# electronic_load_V02_0.net
KiCad netlist of a schematic drawn in EAGLE
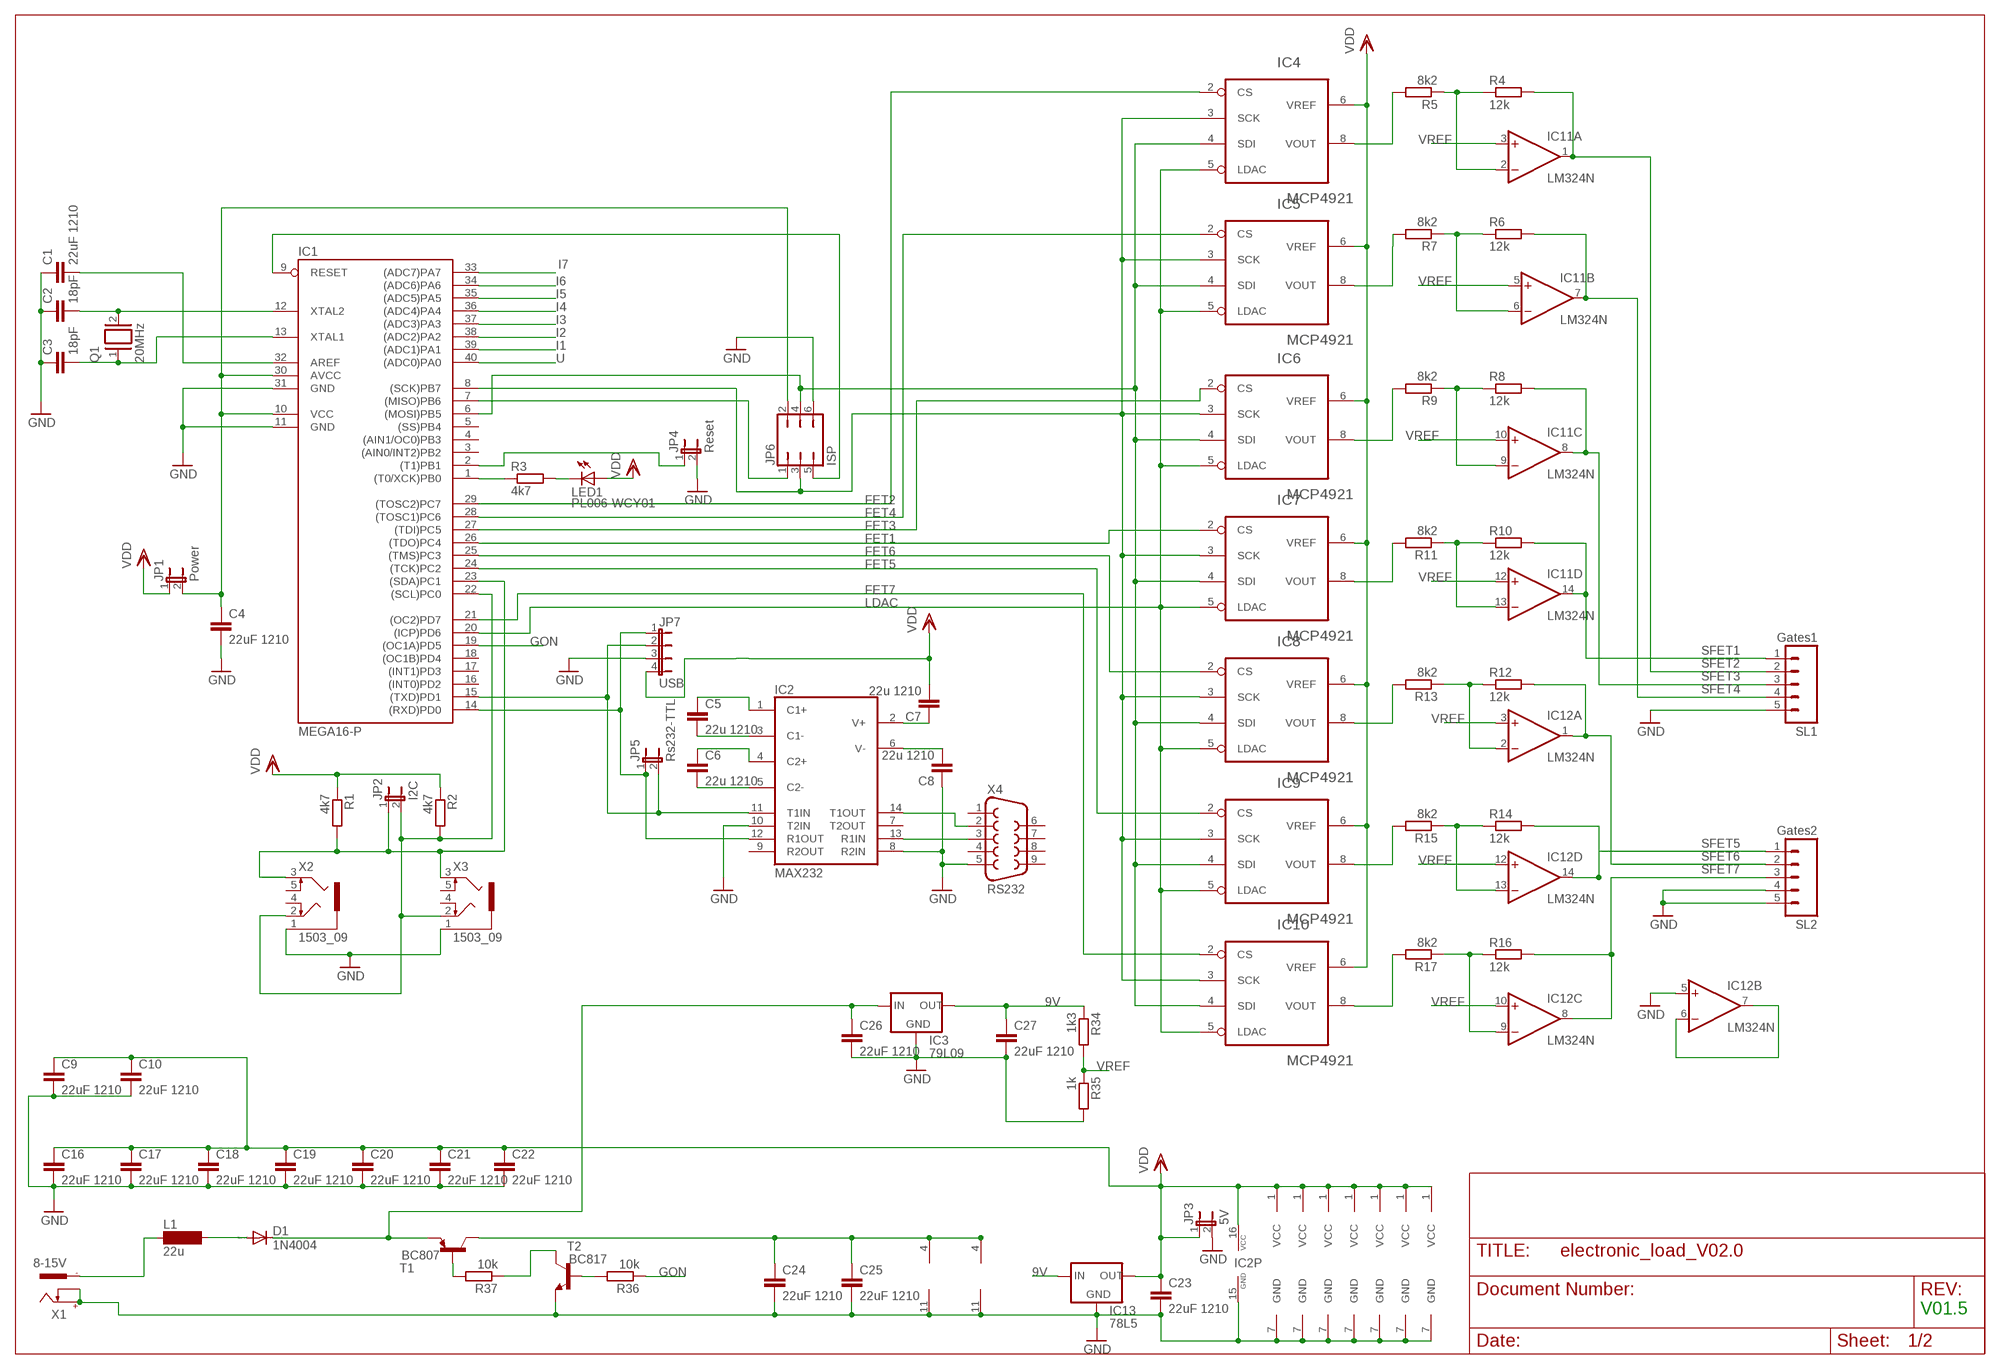
[diagram p0: schematic, sheet 1]
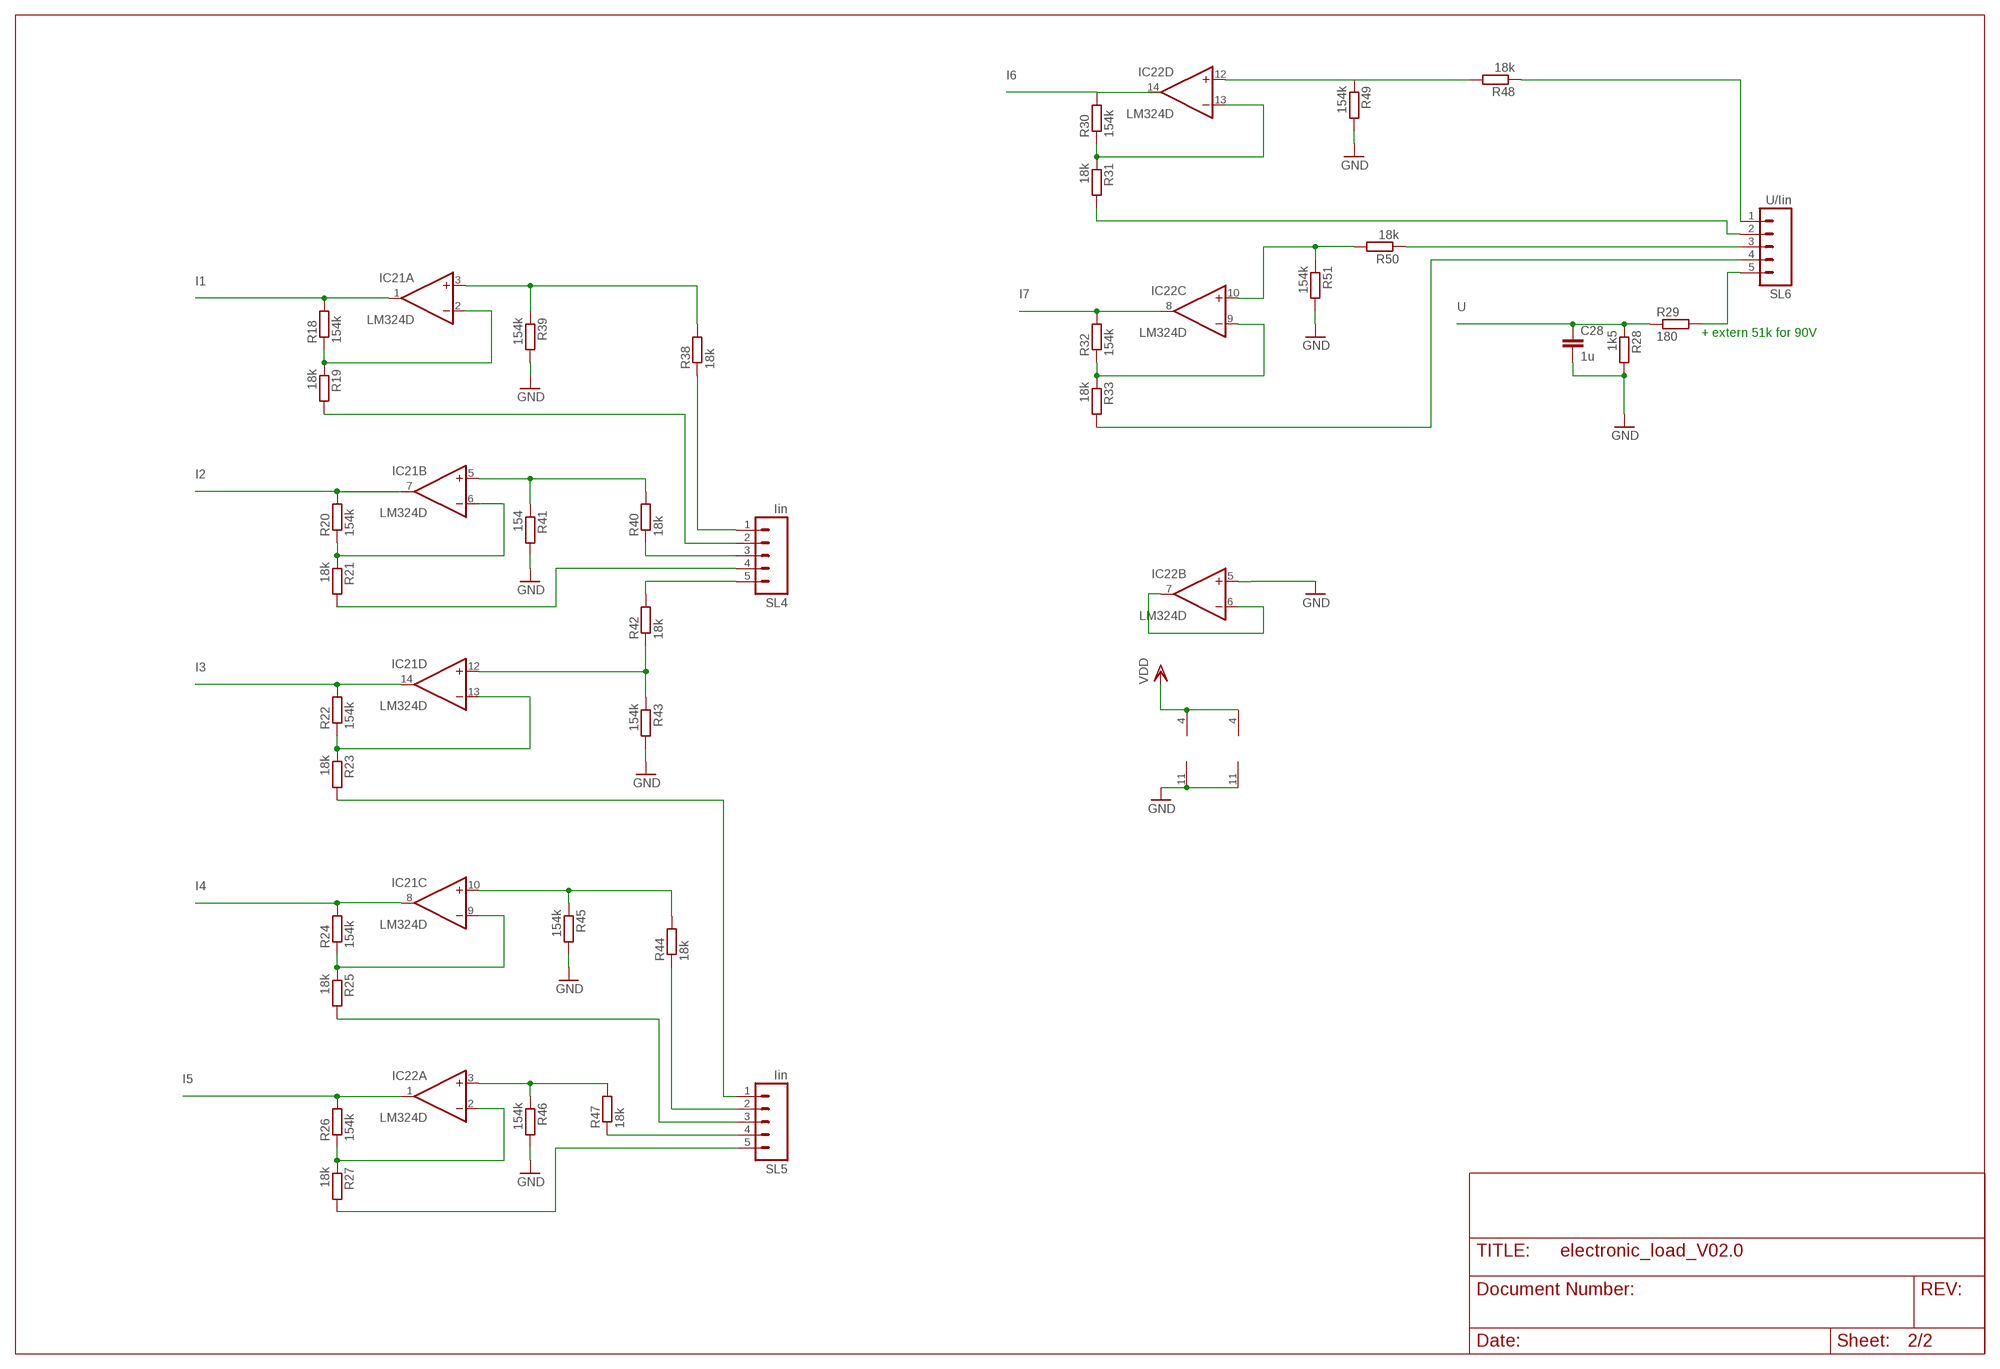
[diagram p1: schematic, sheet 2]

(export (version "E")
  (design (tool "Eeschema 10.0.6"))
  (components
    (comp (ref "C1")
      (value "22uF 1210")
      (footprint "eagle-import:C1206")
      (libsource (lib "eagle-import") (part "C-EUC1206"))
    )
    (comp (ref "C2")
      (value "18pF")
      (footprint "eagle-import:C025-025X050")
      (libsource (lib "eagle-import") (part "resistor_C-EU025-025X050"))
    )
    (comp (ref "C3")
      (value "18pF")
      (footprint "eagle-import:C025-025X050")
      (libsource (lib "eagle-import") (part "resistor_C-EU025-025X050"))
    )
    (comp (ref "C4")
      (value "22uF 1210")
      (footprint "eagle-import:C1206")
      (libsource (lib "eagle-import") (part "C-EUC1206"))
    )
    (comp (ref "C5")
      (value "22u 1210")
      (footprint "eagle-import:C1206")
      (libsource (lib "eagle-import") (part "C-EUC1206"))
    )
    (comp (ref "C6")
      (value "22u 1210")
      (footprint "eagle-import:C1206")
      (libsource (lib "eagle-import") (part "C-EUC1206"))
    )
    (comp (ref "C7")
      (value "22u 1210")
      (footprint "eagle-import:C1206")
      (libsource (lib "eagle-import") (part "C-EUC1206"))
    )
    (comp (ref "C8")
      (value "22u 1210")
      (footprint "eagle-import:C1206")
      (libsource (lib "eagle-import") (part "C-EUC1206"))
    )
    (comp (ref "C9")
      (value "22uF 1210")
      (footprint "eagle-import:C1206")
      (libsource (lib "eagle-import") (part "C-EUC1206"))
    )
    (comp (ref "C10")
      (value "22uF 1210")
      (footprint "eagle-import:C1206")
      (libsource (lib "eagle-import") (part "C-EUC1206"))
    )
    (comp (ref "C16")
      (value "22uF 1210")
      (footprint "eagle-import:C1206")
      (libsource (lib "eagle-import") (part "C-EUC1206"))
    )
    (comp (ref "C17")
      (value "22uF 1210")
      (footprint "eagle-import:C1206")
      (libsource (lib "eagle-import") (part "C-EUC1206"))
    )
    (comp (ref "C18")
      (value "22uF 1210")
      (footprint "eagle-import:C1206")
      (libsource (lib "eagle-import") (part "C-EUC1206"))
    )
    (comp (ref "C19")
      (value "22uF 1210")
      (footprint "eagle-import:C1206")
      (libsource (lib "eagle-import") (part "C-EUC1206"))
    )
    (comp (ref "C20")
      (value "22uF 1210")
      (footprint "eagle-import:C1206")
      (libsource (lib "eagle-import") (part "C-EUC1206"))
    )
    (comp (ref "C21")
      (value "22uF 1210")
      (footprint "eagle-import:C1206")
      (libsource (lib "eagle-import") (part "C-EUC1206"))
    )
    (comp (ref "C22")
      (value "22uF 1210")
      (footprint "eagle-import:C1206")
      (libsource (lib "eagle-import") (part "C-EUC1206"))
    )
    (comp (ref "C23")
      (value "22uF 1210")
      (footprint "eagle-import:C1206")
      (libsource (lib "eagle-import") (part "C-EUC1206"))
    )
    (comp (ref "C24")
      (value "22uF 1210")
      (footprint "eagle-import:C1206")
      (libsource (lib "eagle-import") (part "C-EUC1206"))
    )
    (comp (ref "C25")
      (value "22uF 1210")
      (footprint "eagle-import:C1206")
      (libsource (lib "eagle-import") (part "C-EUC1206"))
    )
    (comp (ref "C26")
      (value "22uF 1210")
      (footprint "eagle-import:C1206")
      (libsource (lib "eagle-import") (part "C-EUC1206"))
    )
    (comp (ref "C27")
      (value "22uF 1210")
      (footprint "eagle-import:C1206")
      (libsource (lib "eagle-import") (part "C-EUC1206"))
    )
    (comp (ref "D1")
      (value "1N4004")
      (footprint "eagle-import:DO41-10")
      (libsource (lib "eagle-import") (part "1N4004"))
    )
    (comp (ref "IC1")
      (value "MEGA16-P")
      (footprint "eagle-import:DIL40")
      (fields (field (name "MPN") "ATMEGA16-16PU"))
      (libsource (lib "eagle-import") (part "MEGA16-P"))
    )
    (comp (ref "IC2")
      (value "MAX232")
      (footprint "eagle-import:DIL16")
      (fields (field (name "MF") "MAXIM") (field (name "MPN") "MAX232ACPE+"))
      (libsource (lib "eagle-import") (part "MAX232"))
    )
    (comp (ref "IC3")
      (value "79L09")
      (footprint "eagle-import:78LXX")
      (libsource (lib "eagle-import") (part "78LXX"))
    )
    (comp (ref "IC4")
      (value "MCP4921")
      (footprint "eagle-import:DIL08")
      (libsource (lib "eagle-import") (part "MCP491"))
    )
    (comp (ref "IC5")
      (value "MCP4921")
      (footprint "eagle-import:DIL08")
      (libsource (lib "eagle-import") (part "MCP491"))
    )
    (comp (ref "IC6")
      (value "MCP4921")
      (footprint "eagle-import:DIL08")
      (libsource (lib "eagle-import") (part "MCP491"))
    )
    (comp (ref "IC7")
      (value "MCP4921")
      (footprint "eagle-import:DIL08")
      (libsource (lib "eagle-import") (part "MCP491"))
    )
    (comp (ref "IC8")
      (value "MCP4921")
      (footprint "eagle-import:DIL08")
      (libsource (lib "eagle-import") (part "MCP491"))
    )
    (comp (ref "IC9")
      (value "MCP4921")
      (footprint "eagle-import:DIL08")
      (libsource (lib "eagle-import") (part "MCP491"))
    )
    (comp (ref "IC10")
      (value "MCP4921")
      (footprint "eagle-import:DIL08")
      (libsource (lib "eagle-import") (part "MCP491"))
    )
    (comp (ref "IC11")
      (value "LM324N")
      (footprint "eagle-import:DIL14")
      (libsource (lib "eagle-import") (part "LM324N"))
    )
    (comp (ref "IC12")
      (value "LM324N")
      (footprint "eagle-import:DIL14")
      (libsource (lib "eagle-import") (part "LM324N"))
    )
    (comp (ref "IC13")
      (value "78L5")
      (footprint "eagle-import:78LXX")
      (libsource (lib "eagle-import") (part "78LXX"))
    )
    (comp (ref "JP1")
      (value "Power")
      (footprint "eagle-import:JP1")
      (libsource (lib "eagle-import") (part "JP1E"))
    )
    (comp (ref "JP2")
      (value "I2C")
      (footprint "eagle-import:JP1")
      (libsource (lib "eagle-import") (part "JP1E"))
    )
    (comp (ref "JP3")
      (value "5V")
      (footprint "eagle-import:JP1")
      (libsource (lib "eagle-import") (part "JP1E"))
    )
    (comp (ref "JP4")
      (value "Reset")
      (footprint "eagle-import:JP1")
      (libsource (lib "eagle-import") (part "JP1E"))
    )
    (comp (ref "JP5")
      (value "Rs232-TTL")
      (footprint "eagle-import:JP1")
      (libsource (lib "eagle-import") (part "JP1E"))
    )
    (comp (ref "JP6")
      (value "ISP")
      (footprint "eagle-import:JP3Q")
      (libsource (lib "eagle-import") (part "JP3Q"))
    )
    (comp (ref "JP7")
      (value "USB")
      (footprint "eagle-import:JP4")
      (libsource (lib "eagle-import") (part "JP4E"))
    )
    (comp (ref "L1")
      (value "22u")
      (footprint "eagle-import:MS85")
      (libsource (lib "eagle-import") (part "MS85"))
    )
    (comp (ref "LED1")
      (value "PL006-WCY01")
      (footprint "eagle-import:SOT23")
      (libsource (lib "eagle-import") (part "PL006-WCY01"))
    )
    (comp (ref "Q1")
      (value "20MHz")
      (footprint "eagle-import:QS")
      (libsource (lib "eagle-import") (part "XTAL/S"))
    )
    (comp (ref "R1")
      (value "4k7")
      (footprint "eagle-import:0207_2V")
      (libsource (lib "eagle-import") (part "R-EU_0207/2V"))
    )
    (comp (ref "R2")
      (value "4k7")
      (footprint "eagle-import:0207_2V")
      (libsource (lib "eagle-import") (part "R-EU_0207/2V"))
    )
    (comp (ref "R3")
      (value "4k7")
      (footprint "eagle-import:R1206")
      (libsource (lib "eagle-import") (part "R-EU_R1206"))
    )
    (comp (ref "R4")
      (value "12k")
      (footprint "eagle-import:R1206")
      (libsource (lib "eagle-import") (part "R-EU_R1206"))
    )
    (comp (ref "R5")
      (value "8k2")
      (footprint "eagle-import:R1206")
      (libsource (lib "eagle-import") (part "R-EU_R1206"))
    )
    (comp (ref "R6")
      (value "12k")
      (footprint "eagle-import:R1206")
      (libsource (lib "eagle-import") (part "R-EU_R1206"))
    )
    (comp (ref "R7")
      (value "8k2")
      (footprint "eagle-import:R1206")
      (libsource (lib "eagle-import") (part "R-EU_R1206"))
    )
    (comp (ref "R8")
      (value "12k")
      (footprint "eagle-import:R1206")
      (libsource (lib "eagle-import") (part "R-EU_R1206"))
    )
    (comp (ref "R9")
      (value "8k2")
      (footprint "eagle-import:R1206")
      (libsource (lib "eagle-import") (part "R-EU_R1206"))
    )
    (comp (ref "R10")
      (value "12k")
      (footprint "eagle-import:R1206")
      (libsource (lib "eagle-import") (part "R-EU_R1206"))
    )
    (comp (ref "R11")
      (value "8k2")
      (footprint "eagle-import:R1206")
      (libsource (lib "eagle-import") (part "R-EU_R1206"))
    )
    (comp (ref "R12")
      (value "12k")
      (footprint "eagle-import:R1206")
      (libsource (lib "eagle-import") (part "R-EU_R1206"))
    )
    (comp (ref "R13")
      (value "8k2")
      (footprint "eagle-import:R1206")
      (libsource (lib "eagle-import") (part "R-EU_R1206"))
    )
    (comp (ref "R14")
      (value "12k")
      (footprint "eagle-import:R1206")
      (libsource (lib "eagle-import") (part "R-EU_R1206"))
    )
    (comp (ref "R15")
      (value "8k2")
      (footprint "eagle-import:R1206")
      (libsource (lib "eagle-import") (part "R-EU_R1206"))
    )
    (comp (ref "R16")
      (value "12k")
      (footprint "eagle-import:R1206")
      (libsource (lib "eagle-import") (part "R-EU_R1206"))
    )
    (comp (ref "R17")
      (value "8k2")
      (footprint "eagle-import:R1206")
      (libsource (lib "eagle-import") (part "R-EU_R1206"))
    )
    (comp (ref "R34")
      (value "1k3")
      (footprint "eagle-import:R1206")
      (libsource (lib "eagle-import") (part "R-EU_R1206"))
    )
    (comp (ref "R35")
      (value "1k")
      (footprint "eagle-import:R1206")
      (libsource (lib "eagle-import") (part "R-EU_R1206"))
    )
    (comp (ref "R36")
      (value "10k")
      (footprint "eagle-import:R1206")
      (libsource (lib "eagle-import") (part "R-EU_R1206"))
    )
    (comp (ref "R37")
      (value "10k")
      (footprint "eagle-import:R1206")
      (libsource (lib "eagle-import") (part "R-EU_R1206"))
    )
    (comp (ref "SL1")
      (value "Gates1")
      (footprint "eagle-import:05P")
      (libsource (lib "eagle-import") (part "M05"))
    )
    (comp (ref "SL2")
      (value "Gates2")
      (footprint "eagle-import:05P")
      (libsource (lib "eagle-import") (part "M05"))
    )
    (comp (ref "T1")
      (value "BC807")
      (footprint "eagle-import:SOT23-BEC")
      (libsource (lib "eagle-import") (part "-PNP-SOT23-BECBC807-16"))
    )
    (comp (ref "T2")
      (value "BC817")
      (footprint "eagle-import:SOT23-BEC")
      (libsource (lib "eagle-import") (part "-NPN-SOT23-BECBC817-16"))
    )
    (comp (ref "X1")
      (value "8-15V")
      (footprint "eagle-import:737992-5")
      (libsource (lib "eagle-import") (part "737992-55"))
    )
    (comp (ref "X2")
      (value "1503_09")
      (footprint "eagle-import:1503_09")
      (libsource (lib "eagle-import") (part "1503_09"))
    )
    (comp (ref "X3")
      (value "1503_09")
      (footprint "eagle-import:1503_09")
      (libsource (lib "eagle-import") (part "1503_09"))
    )
    (comp (ref "X4")
      (value "RS232")
      (footprint "eagle-import:F09H")
      (libsource (lib "eagle-import") (part "F09H"))
    )
    (comp (ref "C28")
      (value "1u")
      (footprint "eagle-import:C1206")
      (libsource (lib "eagle-import") (part "resistor_C-EUC1206"))
    )
    (comp (ref "IC21")
      (value "LM324D")
      (footprint "eagle-import:SO14")
      (libsource (lib "eagle-import") (part "LM324D"))
    )
    (comp (ref "IC22")
      (value "LM324D")
      (footprint "eagle-import:SO14")
      (libsource (lib "eagle-import") (part "LM324D"))
    )
    (comp (ref "R18")
      (value "154k")
      (footprint "eagle-import:M1206")
      (libsource (lib "eagle-import") (part "R-EU_M1206"))
    )
    (comp (ref "R19")
      (value "18k")
      (footprint "eagle-import:M1206")
      (libsource (lib "eagle-import") (part "R-EU_M1206"))
    )
    (comp (ref "R20")
      (value "154k")
      (footprint "eagle-import:M1206")
      (libsource (lib "eagle-import") (part "R-EU_M1206"))
    )
    (comp (ref "R21")
      (value "18k")
      (footprint "eagle-import:M1206")
      (libsource (lib "eagle-import") (part "R-EU_M1206"))
    )
    (comp (ref "R22")
      (value "154k")
      (footprint "eagle-import:M1206")
      (libsource (lib "eagle-import") (part "R-EU_M1206"))
    )
    (comp (ref "R23")
      (value "18k")
      (footprint "eagle-import:M1206")
      (libsource (lib "eagle-import") (part "R-EU_M1206"))
    )
    (comp (ref "R24")
      (value "154k")
      (footprint "eagle-import:M1206")
      (libsource (lib "eagle-import") (part "R-EU_M1206"))
    )
    (comp (ref "R25")
      (value "18k")
      (footprint "eagle-import:M1206")
      (libsource (lib "eagle-import") (part "R-EU_M1206"))
    )
    (comp (ref "R26")
      (value "154k")
      (footprint "eagle-import:M1206")
      (libsource (lib "eagle-import") (part "R-EU_M1206"))
    )
    (comp (ref "R27")
      (value "18k")
      (footprint "eagle-import:M1206")
      (libsource (lib "eagle-import") (part "R-EU_M1206"))
    )
    (comp (ref "R28")
      (value "1k5")
      (footprint "eagle-import:R1206")
      (libsource (lib "eagle-import") (part "R-EU_R1206"))
    )
    (comp (ref "R29")
      (value "180")
      (footprint "eagle-import:R1206")
      (libsource (lib "eagle-import") (part "R-EU_R1206"))
    )
    (comp (ref "R30")
      (value "154k")
      (footprint "eagle-import:M1206")
      (libsource (lib "eagle-import") (part "R-EU_M1206"))
    )
    (comp (ref "R31")
      (value "18k")
      (footprint "eagle-import:M1206")
      (libsource (lib "eagle-import") (part "R-EU_M1206"))
    )
    (comp (ref "R32")
      (value "154k")
      (footprint "eagle-import:M1206")
      (libsource (lib "eagle-import") (part "R-EU_M1206"))
    )
    (comp (ref "R33")
      (value "18k")
      (footprint "eagle-import:M1206")
      (libsource (lib "eagle-import") (part "R-EU_M1206"))
    )
    (comp (ref "R38")
      (value "18k")
      (footprint "eagle-import:R1206")
      (libsource (lib "eagle-import") (part "R-EU_R1206"))
    )
    (comp (ref "R39")
      (value "154k")
      (footprint "eagle-import:M1206")
      (libsource (lib "eagle-import") (part "R-EU_M1206"))
    )
    (comp (ref "R40")
      (value "18k")
      (footprint "eagle-import:M1206")
      (libsource (lib "eagle-import") (part "R-EU_M1206"))
    )
    (comp (ref "R41")
      (value "154")
      (footprint "eagle-import:M1206")
      (libsource (lib "eagle-import") (part "R-EU_M1206"))
    )
    (comp (ref "R42")
      (value "18k")
      (footprint "eagle-import:M1206")
      (libsource (lib "eagle-import") (part "R-EU_M1206"))
    )
    (comp (ref "R43")
      (value "154k")
      (footprint "eagle-import:M1206")
      (libsource (lib "eagle-import") (part "R-EU_M1206"))
    )
    (comp (ref "R44")
      (value "18k")
      (footprint "eagle-import:M1206")
      (libsource (lib "eagle-import") (part "R-EU_M1206"))
    )
    (comp (ref "R45")
      (value "154k")
      (footprint "eagle-import:M1206")
      (libsource (lib "eagle-import") (part "R-EU_M1206"))
    )
    (comp (ref "R46")
      (value "154k")
      (footprint "eagle-import:M1206")
      (libsource (lib "eagle-import") (part "R-EU_M1206"))
    )
    (comp (ref "R47")
      (value "18k")
      (footprint "eagle-import:M1206")
      (libsource (lib "eagle-import") (part "R-EU_M1206"))
    )
    (comp (ref "R48")
      (value "18k")
      (footprint "eagle-import:M1206")
      (libsource (lib "eagle-import") (part "R-EU_M1206"))
    )
    (comp (ref "R49")
      (value "154k")
      (footprint "eagle-import:M1206")
      (libsource (lib "eagle-import") (part "R-EU_M1206"))
    )
    (comp (ref "R50")
      (value "18k")
      (footprint "eagle-import:M1206")
      (libsource (lib "eagle-import") (part "R-EU_M1206"))
    )
    (comp (ref "R51")
      (value "154k")
      (footprint "eagle-import:M1206")
      (libsource (lib "eagle-import") (part "R-EU_M1206"))
    )
    (comp (ref "SL4")
      (value "Iin")
      (footprint "eagle-import:05P")
      (libsource (lib "eagle-import") (part "M05"))
    )
    (comp (ref "SL5")
      (value "Iin")
      (footprint "eagle-import:05P")
      (libsource (lib "eagle-import") (part "M05"))
    )
    (comp (ref "SL6")
      (value "U/Iin")
      (footprint "eagle-import:05P")
      (libsource (lib "eagle-import") (part "M05"))
    )
  )
  (nets
    (net (code "1") (name "9V") (class "Default")
      (node (ref "C27") (pin "1") (pinfunction "1_1") (pintype "passive"))
      (node (ref "IC13") (pin "IN") (pinfunction "IN_IN") (pintype "input"))
      (node (ref "IC3") (pin "OUT") (pinfunction "OUT_OUT") (pintype "passive"))
      (node (ref "R34") (pin "1") (pinfunction "1_1") (pintype "passive"))
    )
    (net (code "2") (name "FET1") (class "Default")
      (node (ref "IC1") (pin "26") (pinfunction "(TDO)PC4_26") (pintype "bidirectional"))
      (node (ref "IC7") (pin "2") (pinfunction "CS_2") (pintype "input"))
    )
    (net (code "3") (name "FET2") (class "Default")
      (node (ref "IC1") (pin "29") (pinfunction "(TOSC2)PC7_29") (pintype "bidirectional"))
      (node (ref "IC4") (pin "2") (pinfunction "CS_2") (pintype "input"))
    )
    (net (code "4") (name "FET3") (class "Default")
      (node (ref "IC1") (pin "27") (pinfunction "(TDI)PC5_27") (pintype "bidirectional"))
      (node (ref "IC6") (pin "2") (pinfunction "CS_2") (pintype "input"))
    )
    (net (code "5") (name "FET4") (class "Default")
      (node (ref "IC1") (pin "28") (pinfunction "(TOSC1)PC6_28") (pintype "bidirectional"))
      (node (ref "IC5") (pin "2") (pinfunction "CS_2") (pintype "input"))
    )
    (net (code "6") (name "FET5") (class "Default")
      (node (ref "IC1") (pin "24") (pinfunction "(TCK)PC2_24") (pintype "bidirectional"))
      (node (ref "IC9") (pin "2") (pinfunction "CS_2") (pintype "input"))
    )
    (net (code "7") (name "FET6") (class "Default")
      (node (ref "IC1") (pin "25") (pinfunction "(TMS)PC3_25") (pintype "bidirectional"))
      (node (ref "IC8") (pin "2") (pinfunction "CS_2") (pintype "input"))
    )
    (net (code "8") (name "FET7") (class "Default")
      (node (ref "IC1") (pin "21") (pinfunction "(OC2)PD7_21") (pintype "bidirectional"))
      (node (ref "IC10") (pin "2") (pinfunction "CS_2") (pintype "input"))
    )
    (net (code "9") (name "GND") (class "Default")
      (node (ref "C1") (pin "1") (pinfunction "1_1") (pintype "passive"))
      (node (ref "C10") (pin "2") (pinfunction "2_2") (pintype "passive"))
      (node (ref "C16") (pin "2") (pinfunction "2_2") (pintype "passive"))
      (node (ref "C17") (pin "2") (pinfunction "2_2") (pintype "passive"))
      (node (ref "C18") (pin "2") (pinfunction "2_2") (pintype "passive"))
      (node (ref "C19") (pin "2") (pinfunction "2_2") (pintype "passive"))
      (node (ref "C2") (pin "1") (pinfunction "1_1") (pintype "passive"))
      (node (ref "C20") (pin "2") (pinfunction "2_2") (pintype "passive"))
      (node (ref "C21") (pin "2") (pinfunction "2_2") (pintype "passive"))
      (node (ref "C22") (pin "2") (pinfunction "2_2") (pintype "passive"))
      (node (ref "C23") (pin "2") (pinfunction "2_2") (pintype "passive"))
      (node (ref "C24") (pin "2") (pinfunction "2_2") (pintype "passive"))
      (node (ref "C25") (pin "2") (pinfunction "2_2") (pintype "passive"))
      (node (ref "C26") (pin "2") (pinfunction "2_2") (pintype "passive"))
      (node (ref "C27") (pin "2") (pinfunction "2_2") (pintype "passive"))
      (node (ref "C28") (pin "2") (pinfunction "2_2") (pintype "passive"))
      (node (ref "C3") (pin "1") (pinfunction "1_1") (pintype "passive"))
      (node (ref "C4") (pin "2") (pinfunction "2_2") (pintype "passive"))
      (node (ref "C8") (pin "1") (pinfunction "1_1") (pintype "passive"))
      (node (ref "C9") (pin "2") (pinfunction "2_2") (pintype "passive"))
      (node (ref "IC1") (pin "11") (pinfunction "GND_11") (pintype "power_in"))
      (node (ref "IC1") (pin "31") (pinfunction "GND_31") (pintype "power_in"))
      (node (ref "IC10") (pin "7") (pinfunction "GND_7") (pintype "power_in"))
      (node (ref "IC11") (pin "11") (pinfunction "V-_11") (pintype "power_in"))
      (node (ref "IC12") (pin "11") (pinfunction "V-_11") (pintype "power_in"))
      (node (ref "IC12") (pin "5") (pinfunction "+IN_5") (pintype "input"))
      (node (ref "IC13") (pin "GND") (pinfunction "GND_GND") (pintype "input"))
      (node (ref "IC2") (pin "10") (pinfunction "T2IN_10") (pintype "input"))
      (node (ref "IC2") (pin "15") (pinfunction "GND_15") (pintype "power_in"))
      (node (ref "IC2") (pin "8") (pinfunction "R2IN_8") (pintype "input"))
      (node (ref "IC21") (pin "11") (pinfunction "V-_11") (pintype "power_in"))
      (node (ref "IC22") (pin "11") (pinfunction "V-_11") (pintype "power_in"))
      (node (ref "IC22") (pin "5") (pinfunction "+IN_5") (pintype "input"))
      (node (ref "IC3") (pin "GND") (pinfunction "GND_GND") (pintype "input"))
      (node (ref "IC4") (pin "7") (pinfunction "GND_7") (pintype "power_in"))
      (node (ref "IC5") (pin "7") (pinfunction "GND_7") (pintype "power_in"))
      (node (ref "IC6") (pin "7") (pinfunction "GND_7") (pintype "power_in"))
      (node (ref "IC7") (pin "7") (pinfunction "GND_7") (pintype "power_in"))
      (node (ref "IC8") (pin "7") (pinfunction "GND_7") (pintype "power_in"))
      (node (ref "IC9") (pin "7") (pinfunction "GND_7") (pintype "power_in"))
      (node (ref "JP3") (pin "2") (pinfunction "2_2") (pintype "passive"))
      (node (ref "JP4") (pin "2") (pinfunction "2_2") (pintype "passive"))
      (node (ref "JP6") (pin "6") (pinfunction "6_6") (pintype "passive"))
      (node (ref "JP7") (pin "3") (pinfunction "3_3") (pintype "passive"))
      (node (ref "R28") (pin "2") (pinfunction "2_2") (pintype "passive"))
      (node (ref "R35") (pin "2") (pinfunction "2_2") (pintype "passive"))
      (node (ref "R39") (pin "2") (pinfunction "2_2") (pintype "passive"))
      (node (ref "R41") (pin "2") (pinfunction "2_2") (pintype "passive"))
      (node (ref "R43") (pin "2") (pinfunction "2_2") (pintype "passive"))
      (node (ref "R45") (pin "2") (pinfunction "2_2") (pintype "passive"))
      (node (ref "R46") (pin "2") (pinfunction "2_2") (pintype "passive"))
      (node (ref "R49") (pin "2") (pinfunction "2_2") (pintype "passive"))
      (node (ref "R51") (pin "2") (pinfunction "2_2") (pintype "passive"))
      (node (ref "SL1") (pin "5") (pinfunction "5_5") (pintype "passive"))
      (node (ref "SL2") (pin "4") (pinfunction "4_4") (pintype "passive"))
      (node (ref "SL2") (pin "5") (pinfunction "5_5") (pintype "passive"))
      (node (ref "T2") (pin "E") (pinfunction "E_E") (pintype "passive"))
      (node (ref "X1") (pin "+") (pinfunction "+_+") (pintype "passive"))
      (node (ref "X1") (pin "K") (pinfunction "K_K") (pintype "passive"))
      (node (ref "X2") (pin "1") (pinfunction "1_1") (pintype "passive"))
      (node (ref "X3") (pin "1") (pinfunction "1_1") (pintype "passive"))
      (node (ref "X4") (pin "5") (pinfunction "5_5") (pintype "passive"))
    )
    (net (code "10") (name "GON") (class "Default")
      (node (ref "IC1") (pin "19") (pinfunction "(OC1A)PD5_19") (pintype "bidirectional"))
      (node (ref "R36") (pin "1") (pinfunction "1_1") (pintype "passive"))
    )
    (net (code "11") (name "I1") (class "Default")
      (node (ref "IC1") (pin "39") (pinfunction "(ADC1)PA1_39") (pintype "bidirectional"))
      (node (ref "IC21") (pin "1") (pinfunction "OUT_1") (pintype "output"))
      (node (ref "R18") (pin "2") (pinfunction "2_2") (pintype "passive"))
    )
    (net (code "12") (name "I2") (class "Default")
      (node (ref "IC1") (pin "38") (pinfunction "(ADC2)PA2_38") (pintype "bidirectional"))
      (node (ref "IC21") (pin "7") (pinfunction "OUT_7") (pintype "output"))
      (node (ref "R20") (pin "2") (pinfunction "2_2") (pintype "passive"))
    )
    (net (code "13") (name "I3") (class "Default")
      (node (ref "IC1") (pin "37") (pinfunction "(ADC3)PA3_37") (pintype "bidirectional"))
      (node (ref "IC21") (pin "14") (pinfunction "OUT_14") (pintype "output"))
      (node (ref "R22") (pin "2") (pinfunction "2_2") (pintype "passive"))
    )
    (net (code "14") (name "I4") (class "Default")
      (node (ref "IC1") (pin "36") (pinfunction "(ADC4)PA4_36") (pintype "bidirectional"))
      (node (ref "IC21") (pin "8") (pinfunction "OUT_8") (pintype "output"))
      (node (ref "R24") (pin "2") (pinfunction "2_2") (pintype "passive"))
    )
    (net (code "15") (name "I5") (class "Default")
      (node (ref "IC1") (pin "35") (pinfunction "(ADC5)PA5_35") (pintype "bidirectional"))
      (node (ref "IC22") (pin "1") (pinfunction "OUT_1") (pintype "output"))
      (node (ref "R26") (pin "2") (pinfunction "2_2") (pintype "passive"))
    )
    (net (code "16") (name "I6") (class "Default")
      (node (ref "IC1") (pin "34") (pinfunction "(ADC6)PA6_34") (pintype "bidirectional"))
      (node (ref "IC22") (pin "14") (pinfunction "OUT_14") (pintype "output"))
      (node (ref "R30") (pin "2") (pinfunction "2_2") (pintype "passive"))
    )
    (net (code "17") (name "I7") (class "Default")
      (node (ref "IC1") (pin "33") (pinfunction "(ADC7)PA7_33") (pintype "bidirectional"))
      (node (ref "IC22") (pin "8") (pinfunction "OUT_8") (pintype "output"))
      (node (ref "R32") (pin "2") (pinfunction "2_2") (pintype "passive"))
    )
    (net (code "18") (name "LDAC") (class "Default")
      (node (ref "IC1") (pin "20") (pinfunction "(ICP)PD6_20") (pintype "bidirectional"))
      (node (ref "IC10") (pin "5") (pinfunction "LDAC_5") (pintype "input"))
      (node (ref "IC4") (pin "5") (pinfunction "LDAC_5") (pintype "input"))
      (node (ref "IC5") (pin "5") (pinfunction "LDAC_5") (pintype "input"))
      (node (ref "IC6") (pin "5") (pinfunction "LDAC_5") (pintype "input"))
      (node (ref "IC7") (pin "5") (pinfunction "LDAC_5") (pintype "input"))
      (node (ref "IC8") (pin "5") (pinfunction "LDAC_5") (pintype "input"))
      (node (ref "IC9") (pin "5") (pinfunction "LDAC_5") (pintype "input"))
    )
    (net (code "19") (name "Net-(C26-Pad1)") (class "Default")
      (node (ref "C26") (pin "1") (pinfunction "1_1") (pintype "passive"))
      (node (ref "D1") (pin "C") (pinfunction "C_C") (pintype "passive"))
      (node (ref "IC3") (pin "IN") (pinfunction "IN_IN") (pintype "input"))
      (node (ref "T1") (pin "E") (pinfunction "E_E") (pintype "passive"))
    )
    (net (code "20") (name "Net-(D1-PadA)") (class "Default")
      (node (ref "D1") (pin "A") (pinfunction "A_A") (pintype "passive"))
      (node (ref "L1") (pin "2") (pinfunction "2_2") (pintype "passive"))
    )
    (net (code "21") (name "Net-(IC1-(MISO)PB6)") (class "Default")
      (node (ref "IC1") (pin "7") (pinfunction "(MISO)PB6_7") (pintype "bidirectional"))
      (node (ref "JP6") (pin "1") (pinfunction "1_1") (pintype "passive"))
    )
    (net (code "22") (name "Net-(IC1-(MOSI)PB5)") (class "Default")
      (node (ref "IC1") (pin "6") (pinfunction "(MOSI)PB5_6") (pintype "bidirectional"))
      (node (ref "IC10") (pin "4") (pinfunction "SDI_4") (pintype "input"))
      (node (ref "IC4") (pin "4") (pinfunction "SDI_4") (pintype "input"))
      (node (ref "IC5") (pin "4") (pinfunction "SDI_4") (pintype "input"))
      (node (ref "IC6") (pin "4") (pinfunction "SDI_4") (pintype "input"))
      (node (ref "IC7") (pin "4") (pinfunction "SDI_4") (pintype "input"))
      (node (ref "IC8") (pin "4") (pinfunction "SDI_4") (pintype "input"))
      (node (ref "IC9") (pin "4") (pinfunction "SDI_4") (pintype "input"))
      (node (ref "JP6") (pin "4") (pinfunction "4_4") (pintype "passive"))
    )
    (net (code "23") (name "Net-(IC1-(RXD)PD0)") (class "Default")
      (node (ref "IC1") (pin "14") (pinfunction "(RXD)PD0_14") (pintype "bidirectional"))
      (node (ref "IC2") (pin "12") (pinfunction "R1OUT_12") (pintype "output"))
      (node (ref "JP5") (pin "1") (pinfunction "1_1") (pintype "passive"))
      (node (ref "JP7") (pin "1") (pinfunction "1_1") (pintype "passive"))
    )
    (net (code "24") (name "Net-(IC1-(SCK)PB7)") (class "Default")
      (node (ref "IC1") (pin "8") (pinfunction "(SCK)PB7_8") (pintype "bidirectional"))
      (node (ref "IC10") (pin "3") (pinfunction "SCK_3") (pintype "input"))
      (node (ref "IC4") (pin "3") (pinfunction "SCK_3") (pintype "input"))
      (node (ref "IC5") (pin "3") (pinfunction "SCK_3") (pintype "input"))
      (node (ref "IC6") (pin "3") (pinfunction "SCK_3") (pintype "input"))
      (node (ref "IC7") (pin "3") (pinfunction "SCK_3") (pintype "input"))
      (node (ref "IC8") (pin "3") (pinfunction "SCK_3") (pintype "input"))
      (node (ref "IC9") (pin "3") (pinfunction "SCK_3") (pintype "input"))
      (node (ref "JP6") (pin "3") (pinfunction "3_3") (pintype "passive"))
    )
    (net (code "25") (name "Net-(IC1-(SCL)PC0)") (class "Default")
      (node (ref "IC1") (pin "22") (pinfunction "(SCL)PC0_22") (pintype "bidirectional"))
      (node (ref "JP2") (pin "2") (pinfunction "2_2") (pintype "passive"))
      (node (ref "R2") (pin "2") (pinfunction "2_2") (pintype "passive"))
      (node (ref "X2") (pin "2") (pinfunction "2_2") (pintype "passive"))
      (node (ref "X3") (pin "2") (pinfunction "2_2") (pintype "passive"))
    )
    (net (code "26") (name "Net-(IC1-(SDA)PC1)") (class "Default")
      (node (ref "IC1") (pin "23") (pinfunction "(SDA)PC1_23") (pintype "bidirectional"))
      (node (ref "JP2") (pin "1") (pinfunction "1_1") (pintype "passive"))
      (node (ref "R1") (pin "2") (pinfunction "2_2") (pintype "passive"))
      (node (ref "X2") (pin "3") (pinfunction "3_3") (pintype "passive"))
      (node (ref "X3") (pin "3") (pinfunction "3_3") (pintype "passive"))
    )
    (net (code "27") (name "Net-(IC1-(T0{slash}XCK)PB0)") (class "Default")
      (node (ref "IC1") (pin "1") (pinfunction "(T0/XCK)PB0_1") (pintype "bidirectional"))
      (node (ref "R3") (pin "1") (pinfunction "1_1") (pintype "passive"))
    )
    (net (code "28") (name "Net-(IC1-(T1)PB1)") (class "Default")
      (node (ref "IC1") (pin "2") (pinfunction "(T1)PB1_2") (pintype "bidirectional"))
      (node (ref "JP4") (pin "1") (pinfunction "1_1") (pintype "passive"))
    )
    (net (code "29") (name "Net-(IC1-(TXD)PD1)") (class "Default")
      (node (ref "IC1") (pin "15") (pinfunction "(TXD)PD1_15") (pintype "bidirectional"))
      (node (ref "IC2") (pin "11") (pinfunction "T1IN_11") (pintype "input"))
      (node (ref "JP5") (pin "2") (pinfunction "2_2") (pintype "passive"))
      (node (ref "JP7") (pin "2") (pinfunction "2_2") (pintype "passive"))
    )
    (net (code "30") (name "Net-(IC1-AREF)") (class "Default")
      (node (ref "C1") (pin "2") (pinfunction "2_2") (pintype "passive"))
      (node (ref "IC1") (pin "32") (pinfunction "AREF_32") (pintype "passive"))
    )
    (net (code "31") (name "Net-(IC1-AVCC)") (class "Default")
      (node (ref "C4") (pin "1") (pinfunction "1_1") (pintype "passive"))
      (node (ref "IC1") (pin "10") (pinfunction "VCC_10") (pintype "power_in"))
      (node (ref "IC1") (pin "30") (pinfunction "AVCC_30") (pintype "power_in"))
      (node (ref "JP1") (pin "2") (pinfunction "2_2") (pintype "passive"))
      (node (ref "JP6") (pin "2") (pinfunction "2_2") (pintype "passive"))
    )
    (net (code "32") (name "Net-(IC1-RESET)") (class "Default")
      (node (ref "IC1") (pin "9") (pinfunction "RESET_9") (pintype "input"))
      (node (ref "JP6") (pin "5") (pinfunction "5_5") (pintype "passive"))
    )
    (net (code "33") (name "Net-(IC1-XTAL1)") (class "Default")
      (node (ref "C3") (pin "2") (pinfunction "2_2") (pintype "passive"))
      (node (ref "IC1") (pin "13") (pinfunction "XTAL1_13") (pintype "bidirectional"))
      (node (ref "Q1") (pin "1") (pinfunction "1_1") (pintype "passive"))
    )
    (net (code "34") (name "Net-(IC1-XTAL2)") (class "Default")
      (node (ref "C2") (pin "2") (pinfunction "2_2") (pintype "passive"))
      (node (ref "IC1") (pin "12") (pinfunction "XTAL2_12") (pintype "bidirectional"))
      (node (ref "Q1") (pin "2") (pinfunction "2_2") (pintype "passive"))
    )
    (net (code "35") (name "Net-(IC2A-C1+)") (class "Default")
      (node (ref "C5") (pin "1") (pinfunction "1_1") (pintype "passive"))
      (node (ref "IC2") (pin "1") (pinfunction "C1+_1") (pintype "bidirectional"))
    )
    (net (code "36") (name "Net-(IC2A-C1-)") (class "Default")
      (node (ref "C5") (pin "2") (pinfunction "2_2") (pintype "passive"))
      (node (ref "IC2") (pin "3") (pinfunction "C1-_3") (pintype "bidirectional"))
    )
    (net (code "37") (name "Net-(IC2A-C2+)") (class "Default")
      (node (ref "C6") (pin "1") (pinfunction "1_1") (pintype "passive"))
      (node (ref "IC2") (pin "4") (pinfunction "C2+_4") (pintype "bidirectional"))
    )
    (net (code "38") (name "Net-(IC2A-C2-)") (class "Default")
      (node (ref "C6") (pin "2") (pinfunction "2_2") (pintype "passive"))
      (node (ref "IC2") (pin "5") (pinfunction "C2-_5") (pintype "bidirectional"))
    )
    (net (code "39") (name "Net-(IC2A-R1IN)") (class "Default")
      (node (ref "IC2") (pin "13") (pinfunction "R1IN_13") (pintype "input"))
      (node (ref "X4") (pin "3") (pinfunction "3_3") (pintype "passive"))
    )
    (net (code "40") (name "Net-(IC2A-T1OUT)") (class "Default")
      (node (ref "IC2") (pin "14") (pinfunction "T1OUT_14") (pintype "output"))
      (node (ref "X4") (pin "2") (pinfunction "2_2") (pintype "passive"))
    )
    (net (code "41") (name "Net-(IC2A-V+)") (class "Default")
      (node (ref "C7") (pin "1") (pinfunction "1_1") (pintype "passive"))
      (node (ref "IC2") (pin "2") (pinfunction "V+_2") (pintype "bidirectional"))
    )
    (net (code "42") (name "Net-(IC2A-V-)") (class "Default")
      (node (ref "C8") (pin "2") (pinfunction "2_2") (pintype "passive"))
      (node (ref "IC2") (pin "6") (pinfunction "V-_6") (pintype "bidirectional"))
    )
    (net (code "43") (name "Net-(IC4A-VOUT)") (class "Default")
      (node (ref "IC4") (pin "8") (pinfunction "VOUT_8") (pintype "output"))
      (node (ref "R5") (pin "2") (pinfunction "2_2") (pintype "passive"))
    )
    (net (code "44") (name "Net-(IC5A-VOUT)") (class "Default")
      (node (ref "IC5") (pin "8") (pinfunction "VOUT_8") (pintype "output"))
      (node (ref "R7") (pin "2") (pinfunction "2_2") (pintype "passive"))
    )
    (net (code "45") (name "Net-(IC6A-VOUT)") (class "Default")
      (node (ref "IC6") (pin "8") (pinfunction "VOUT_8") (pintype "output"))
      (node (ref "R9") (pin "2") (pinfunction "2_2") (pintype "passive"))
    )
    (net (code "46") (name "Net-(IC7A-VOUT)") (class "Default")
      (node (ref "IC7") (pin "8") (pinfunction "VOUT_8") (pintype "output"))
      (node (ref "R11") (pin "2") (pinfunction "2_2") (pintype "passive"))
    )
    (net (code "47") (name "Net-(IC8A-VOUT)") (class "Default")
      (node (ref "IC8") (pin "8") (pinfunction "VOUT_8") (pintype "output"))
      (node (ref "R13") (pin "2") (pinfunction "2_2") (pintype "passive"))
    )
    (net (code "48") (name "Net-(IC9A-VOUT)") (class "Default")
      (node (ref "IC9") (pin "8") (pinfunction "VOUT_8") (pintype "output"))
      (node (ref "R15") (pin "2") (pinfunction "2_2") (pintype "passive"))
    )
    (net (code "49") (name "Net-(IC10A-VOUT)") (class "Default")
      (node (ref "IC10") (pin "8") (pinfunction "VOUT_8") (pintype "output"))
      (node (ref "R17") (pin "2") (pinfunction "2_2") (pintype "passive"))
    )
    (net (code "50") (name "Net-(IC11A--IN)") (class "Default")
      (node (ref "IC11") (pin "2") (pinfunction "-IN_2") (pintype "input"))
      (node (ref "R4") (pin "1") (pinfunction "1_1") (pintype "passive"))
      (node (ref "R5") (pin "1") (pinfunction "1_1") (pintype "passive"))
    )
    (net (code "51") (name "Net-(IC11B--IN)") (class "Default")
      (node (ref "IC11") (pin "6") (pinfunction "-IN_6") (pintype "input"))
      (node (ref "R6") (pin "1") (pinfunction "1_1") (pintype "passive"))
      (node (ref "R7") (pin "1") (pinfunction "1_1") (pintype "passive"))
    )
    (net (code "52") (name "Net-(IC11C--IN)") (class "Default")
      (node (ref "IC11") (pin "9") (pinfunction "-IN_9") (pintype "input"))
      (node (ref "R8") (pin "1") (pinfunction "1_1") (pintype "passive"))
      (node (ref "R9") (pin "1") (pinfunction "1_1") (pintype "passive"))
    )
    (net (code "53") (name "Net-(IC11D--IN)") (class "Default")
      (node (ref "IC11") (pin "13") (pinfunction "-IN_13") (pintype "input"))
      (node (ref "R10") (pin "1") (pinfunction "1_1") (pintype "passive"))
      (node (ref "R11") (pin "1") (pinfunction "1_1") (pintype "passive"))
    )
    (net (code "54") (name "Net-(IC11E-V+)") (class "Default")
      (node (ref "C24") (pin "1") (pinfunction "1_1") (pintype "passive"))
      (node (ref "C25") (pin "1") (pinfunction "1_1") (pintype "passive"))
      (node (ref "IC11") (pin "4") (pinfunction "V+_4") (pintype "power_in"))
      (node (ref "IC12") (pin "4") (pinfunction "V+_4") (pintype "power_in"))
      (node (ref "T1") (pin "C") (pinfunction "C_C") (pintype "passive"))
    )
    (net (code "55") (name "Net-(IC12A--IN)") (class "Default")
      (node (ref "IC12") (pin "2") (pinfunction "-IN_2") (pintype "input"))
      (node (ref "R12") (pin "1") (pinfunction "1_1") (pintype "passive"))
      (node (ref "R13") (pin "1") (pinfunction "1_1") (pintype "passive"))
    )
    (net (code "56") (name "Net-(IC12B--IN)") (class "Default")
      (node (ref "IC12") (pin "6") (pinfunction "-IN_6") (pintype "input"))
      (node (ref "IC12") (pin "7") (pinfunction "OUT_7") (pintype "output"))
    )
    (net (code "57") (name "Net-(IC12C--IN)") (class "Default")
      (node (ref "IC12") (pin "9") (pinfunction "-IN_9") (pintype "input"))
      (node (ref "R16") (pin "1") (pinfunction "1_1") (pintype "passive"))
      (node (ref "R17") (pin "1") (pinfunction "1_1") (pintype "passive"))
    )
    (net (code "58") (name "Net-(IC12D--IN)") (class "Default")
      (node (ref "IC12") (pin "13") (pinfunction "-IN_13") (pintype "input"))
      (node (ref "R14") (pin "1") (pinfunction "1_1") (pintype "passive"))
      (node (ref "R15") (pin "1") (pinfunction "1_1") (pintype "passive"))
    )
    (net (code "59") (name "Net-(IC21A-+IN)") (class "Default")
      (node (ref "IC21") (pin "3") (pinfunction "+IN_3") (pintype "input"))
      (node (ref "R38") (pin "2") (pinfunction "2_2") (pintype "passive"))
      (node (ref "R39") (pin "1") (pinfunction "1_1") (pintype "passive"))
    )
    (net (code "60") (name "Net-(IC21A--IN)") (class "Default")
      (node (ref "IC21") (pin "2") (pinfunction "-IN_2") (pintype "input"))
      (node (ref "R18") (pin "1") (pinfunction "1_1") (pintype "passive"))
      (node (ref "R19") (pin "1") (pinfunction "1_1") (pintype "passive"))
    )
    (net (code "61") (name "Net-(IC21B-+IN)") (class "Default")
      (node (ref "IC21") (pin "5") (pinfunction "+IN_5") (pintype "input"))
      (node (ref "R40") (pin "2") (pinfunction "2_2") (pintype "passive"))
      (node (ref "R41") (pin "1") (pinfunction "1_1") (pintype "passive"))
    )
    (net (code "62") (name "Net-(IC21B--IN)") (class "Default")
      (node (ref "IC21") (pin "6") (pinfunction "-IN_6") (pintype "input"))
      (node (ref "R20") (pin "1") (pinfunction "1_1") (pintype "passive"))
      (node (ref "R21") (pin "1") (pinfunction "1_1") (pintype "passive"))
    )
    (net (code "63") (name "Net-(IC21C-+IN)") (class "Default")
      (node (ref "IC21") (pin "10") (pinfunction "+IN_10") (pintype "input"))
      (node (ref "R44") (pin "2") (pinfunction "2_2") (pintype "passive"))
      (node (ref "R45") (pin "1") (pinfunction "1_1") (pintype "passive"))
    )
    (net (code "64") (name "Net-(IC21C--IN)") (class "Default")
      (node (ref "IC21") (pin "9") (pinfunction "-IN_9") (pintype "input"))
      (node (ref "R24") (pin "1") (pinfunction "1_1") (pintype "passive"))
      (node (ref "R25") (pin "1") (pinfunction "1_1") (pintype "passive"))
    )
    (net (code "65") (name "Net-(IC21D-+IN)") (class "Default")
      (node (ref "IC21") (pin "12") (pinfunction "+IN_12") (pintype "input"))
      (node (ref "R42") (pin "1") (pinfunction "1_1") (pintype "passive"))
      (node (ref "R43") (pin "1") (pinfunction "1_1") (pintype "passive"))
    )
    (net (code "66") (name "Net-(IC21D--IN)") (class "Default")
      (node (ref "IC21") (pin "13") (pinfunction "-IN_13") (pintype "input"))
      (node (ref "R22") (pin "1") (pinfunction "1_1") (pintype "passive"))
      (node (ref "R23") (pin "1") (pinfunction "1_1") (pintype "passive"))
    )
    (net (code "67") (name "Net-(IC22A-+IN)") (class "Default")
      (node (ref "IC22") (pin "3") (pinfunction "+IN_3") (pintype "input"))
      (node (ref "R46") (pin "1") (pinfunction "1_1") (pintype "passive"))
      (node (ref "R47") (pin "2") (pinfunction "2_2") (pintype "passive"))
    )
    (net (code "68") (name "Net-(IC22A--IN)") (class "Default")
      (node (ref "IC22") (pin "2") (pinfunction "-IN_2") (pintype "input"))
      (node (ref "R26") (pin "1") (pinfunction "1_1") (pintype "passive"))
      (node (ref "R27") (pin "1") (pinfunction "1_1") (pintype "passive"))
    )
    (net (code "69") (name "Net-(IC22B--IN)") (class "Default")
      (node (ref "IC22") (pin "6") (pinfunction "-IN_6") (pintype "input"))
      (node (ref "IC22") (pin "7") (pinfunction "OUT_7") (pintype "output"))
    )
    (net (code "70") (name "Net-(IC22C-+IN)") (class "Default")
      (node (ref "IC22") (pin "10") (pinfunction "+IN_10") (pintype "input"))
      (node (ref "R50") (pin "2") (pinfunction "2_2") (pintype "passive"))
      (node (ref "R51") (pin "1") (pinfunction "1_1") (pintype "passive"))
    )
    (net (code "71") (name "Net-(IC22C--IN)") (class "Default")
      (node (ref "IC22") (pin "9") (pinfunction "-IN_9") (pintype "input"))
      (node (ref "R32") (pin "1") (pinfunction "1_1") (pintype "passive"))
      (node (ref "R33") (pin "1") (pinfunction "1_1") (pintype "passive"))
    )
    (net (code "72") (name "Net-(IC22D-+IN)") (class "Default")
      (node (ref "IC22") (pin "12") (pinfunction "+IN_12") (pintype "input"))
      (node (ref "R48") (pin "2") (pinfunction "2_2") (pintype "passive"))
      (node (ref "R49") (pin "1") (pinfunction "1_1") (pintype "passive"))
    )
    (net (code "73") (name "Net-(IC22D--IN)") (class "Default")
      (node (ref "IC22") (pin "13") (pinfunction "-IN_13") (pintype "input"))
      (node (ref "R30") (pin "1") (pinfunction "1_1") (pintype "passive"))
      (node (ref "R31") (pin "1") (pinfunction "1_1") (pintype "passive"))
    )
    (net (code "74") (name "Net-(L1-Pad1)") (class "Default")
      (node (ref "L1") (pin "1") (pinfunction "1_1") (pintype "passive"))
      (node (ref "X1") (pin "-1") (pinfunction "-1_-1") (pintype "passive"))
    )
    (net (code "75") (name "Net-(LED1-C)") (class "Default")
      (node (ref "LED1") (pin "3") (pinfunction "C_3") (pintype "passive"))
      (node (ref "R3") (pin "2") (pinfunction "2_2") (pintype "passive"))
    )
    (net (code "76") (name "Net-(R19-Pad2)") (class "Default")
      (node (ref "R19") (pin "2") (pinfunction "2_2") (pintype "passive"))
      (node (ref "SL4") (pin "2") (pinfunction "2_2") (pintype "passive"))
    )
    (net (code "77") (name "Net-(R21-Pad2)") (class "Default")
      (node (ref "R21") (pin "2") (pinfunction "2_2") (pintype "passive"))
      (node (ref "SL4") (pin "4") (pinfunction "4_4") (pintype "passive"))
    )
    (net (code "78") (name "Net-(R23-Pad2)") (class "Default")
      (node (ref "R23") (pin "2") (pinfunction "2_2") (pintype "passive"))
      (node (ref "SL5") (pin "1") (pinfunction "1_1") (pintype "passive"))
    )
    (net (code "79") (name "Net-(R25-Pad2)") (class "Default")
      (node (ref "R25") (pin "2") (pinfunction "2_2") (pintype "passive"))
      (node (ref "SL5") (pin "3") (pinfunction "3_3") (pintype "passive"))
    )
    (net (code "80") (name "Net-(R27-Pad2)") (class "Default")
      (node (ref "R27") (pin "2") (pinfunction "2_2") (pintype "passive"))
      (node (ref "SL5") (pin "5") (pinfunction "5_5") (pintype "passive"))
    )
    (net (code "81") (name "Net-(R29-Pad2)") (class "Default")
      (node (ref "R29") (pin "2") (pinfunction "2_2") (pintype "passive"))
      (node (ref "SL6") (pin "5") (pinfunction "5_5") (pintype "passive"))
    )
    (net (code "82") (name "Net-(R31-Pad2)") (class "Default")
      (node (ref "R31") (pin "2") (pinfunction "2_2") (pintype "passive"))
      (node (ref "SL6") (pin "2") (pinfunction "2_2") (pintype "passive"))
    )
    (net (code "83") (name "Net-(R33-Pad2)") (class "Default")
      (node (ref "R33") (pin "2") (pinfunction "2_2") (pintype "passive"))
      (node (ref "SL6") (pin "4") (pinfunction "4_4") (pintype "passive"))
    )
    (net (code "84") (name "Net-(R36-Pad2)") (class "Default")
      (node (ref "R36") (pin "2") (pinfunction "2_2") (pintype "passive"))
      (node (ref "T2") (pin "B") (pinfunction "B_B") (pintype "passive"))
    )
    (net (code "85") (name "Net-(R37-Pad1)") (class "Default")
      (node (ref "R37") (pin "1") (pinfunction "1_1") (pintype "passive"))
      (node (ref "T2") (pin "C") (pinfunction "C_C") (pintype "passive"))
    )
    (net (code "86") (name "Net-(R37-Pad2)") (class "Default")
      (node (ref "R37") (pin "2") (pinfunction "2_2") (pintype "passive"))
      (node (ref "T1") (pin "B") (pinfunction "B_B") (pintype "passive"))
    )
    (net (code "87") (name "Net-(R38-Pad1)") (class "Default")
      (node (ref "R38") (pin "1") (pinfunction "1_1") (pintype "passive"))
      (node (ref "SL4") (pin "1") (pinfunction "1_1") (pintype "passive"))
    )
    (net (code "88") (name "Net-(R40-Pad1)") (class "Default")
      (node (ref "R40") (pin "1") (pinfunction "1_1") (pintype "passive"))
      (node (ref "SL4") (pin "3") (pinfunction "3_3") (pintype "passive"))
    )
    (net (code "89") (name "Net-(R42-Pad2)") (class "Default")
      (node (ref "R42") (pin "2") (pinfunction "2_2") (pintype "passive"))
      (node (ref "SL4") (pin "5") (pinfunction "5_5") (pintype "passive"))
    )
    (net (code "90") (name "Net-(R44-Pad1)") (class "Default")
      (node (ref "R44") (pin "1") (pinfunction "1_1") (pintype "passive"))
      (node (ref "SL5") (pin "2") (pinfunction "2_2") (pintype "passive"))
    )
    (net (code "91") (name "Net-(R47-Pad1)") (class "Default")
      (node (ref "R47") (pin "1") (pinfunction "1_1") (pintype "passive"))
      (node (ref "SL5") (pin "4") (pinfunction "4_4") (pintype "passive"))
    )
    (net (code "92") (name "Net-(R48-Pad1)") (class "Default")
      (node (ref "R48") (pin "1") (pinfunction "1_1") (pintype "passive"))
      (node (ref "SL6") (pin "1") (pinfunction "1_1") (pintype "passive"))
    )
    (net (code "93") (name "Net-(R50-Pad1)") (class "Default")
      (node (ref "R50") (pin "1") (pinfunction "1_1") (pintype "passive"))
      (node (ref "SL6") (pin "3") (pinfunction "3_3") (pintype "passive"))
    )
    (net (code "94") (name "SFET1") (class "Default")
      (node (ref "IC11") (pin "14") (pinfunction "OUT_14") (pintype "output"))
      (node (ref "R10") (pin "2") (pinfunction "2_2") (pintype "passive"))
      (node (ref "SL1") (pin "1") (pinfunction "1_1") (pintype "passive"))
    )
    (net (code "95") (name "SFET2") (class "Default")
      (node (ref "IC11") (pin "1") (pinfunction "OUT_1") (pintype "output"))
      (node (ref "R4") (pin "2") (pinfunction "2_2") (pintype "passive"))
      (node (ref "SL1") (pin "2") (pinfunction "2_2") (pintype "passive"))
    )
    (net (code "96") (name "SFET3") (class "Default")
      (node (ref "IC11") (pin "8") (pinfunction "OUT_8") (pintype "output"))
      (node (ref "R8") (pin "2") (pinfunction "2_2") (pintype "passive"))
      (node (ref "SL1") (pin "3") (pinfunction "3_3") (pintype "passive"))
    )
    (net (code "97") (name "SFET4") (class "Default")
      (node (ref "IC11") (pin "7") (pinfunction "OUT_7") (pintype "output"))
      (node (ref "R6") (pin "2") (pinfunction "2_2") (pintype "passive"))
      (node (ref "SL1") (pin "4") (pinfunction "4_4") (pintype "passive"))
    )
    (net (code "98") (name "SFET5") (class "Default")
      (node (ref "IC12") (pin "14") (pinfunction "OUT_14") (pintype "output"))
      (node (ref "R14") (pin "2") (pinfunction "2_2") (pintype "passive"))
      (node (ref "SL2") (pin "1") (pinfunction "1_1") (pintype "passive"))
    )
    (net (code "99") (name "SFET6") (class "Default")
      (node (ref "IC12") (pin "1") (pinfunction "OUT_1") (pintype "output"))
      (node (ref "R12") (pin "2") (pinfunction "2_2") (pintype "passive"))
      (node (ref "SL2") (pin "2") (pinfunction "2_2") (pintype "passive"))
    )
    (net (code "100") (name "SFET7") (class "Default")
      (node (ref "IC12") (pin "8") (pinfunction "OUT_8") (pintype "output"))
      (node (ref "R16") (pin "2") (pinfunction "2_2") (pintype "passive"))
      (node (ref "SL2") (pin "3") (pinfunction "3_3") (pintype "passive"))
    )
    (net (code "101") (name "U") (class "Default")
      (node (ref "C28") (pin "1") (pinfunction "1_1") (pintype "passive"))
      (node (ref "IC1") (pin "40") (pinfunction "(ADC0)PA0_40") (pintype "bidirectional"))
      (node (ref "R28") (pin "1") (pinfunction "1_1") (pintype "passive"))
      (node (ref "R29") (pin "1") (pinfunction "1_1") (pintype "passive"))
    )
    (net (code "102") (name "VDD") (class "Default")
      (node (ref "C10") (pin "1") (pinfunction "1_1") (pintype "passive"))
      (node (ref "C16") (pin "1") (pinfunction "1_1") (pintype "passive"))
      (node (ref "C17") (pin "1") (pinfunction "1_1") (pintype "passive"))
      (node (ref "C18") (pin "1") (pinfunction "1_1") (pintype "passive"))
      (node (ref "C19") (pin "1") (pinfunction "1_1") (pintype "passive"))
      (node (ref "C20") (pin "1") (pinfunction "1_1") (pintype "passive"))
      (node (ref "C21") (pin "1") (pinfunction "1_1") (pintype "passive"))
      (node (ref "C22") (pin "1") (pinfunction "1_1") (pintype "passive"))
      (node (ref "C23") (pin "1") (pinfunction "1_1") (pintype "passive"))
      (node (ref "C7") (pin "2") (pinfunction "2_2") (pintype "passive"))
      (node (ref "C9") (pin "1") (pinfunction "1_1") (pintype "passive"))
      (node (ref "IC10") (pin "1") (pinfunction "VCC_1") (pintype "power_in"))
      (node (ref "IC10") (pin "6") (pinfunction "VREF_6") (pintype "input"))
      (node (ref "IC13") (pin "OUT") (pinfunction "OUT_OUT") (pintype "passive"))
      (node (ref "IC2") (pin "16") (pinfunction "VCC_16") (pintype "power_in"))
      (node (ref "IC21") (pin "4") (pinfunction "V+_4") (pintype "power_in"))
      (node (ref "IC22") (pin "4") (pinfunction "V+_4") (pintype "power_in"))
      (node (ref "IC4") (pin "1") (pinfunction "VCC_1") (pintype "power_in"))
      (node (ref "IC4") (pin "6") (pinfunction "VREF_6") (pintype "input"))
      (node (ref "IC5") (pin "1") (pinfunction "VCC_1") (pintype "power_in"))
      (node (ref "IC5") (pin "6") (pinfunction "VREF_6") (pintype "input"))
      (node (ref "IC6") (pin "1") (pinfunction "VCC_1") (pintype "power_in"))
      (node (ref "IC6") (pin "6") (pinfunction "VREF_6") (pintype "input"))
      (node (ref "IC7") (pin "1") (pinfunction "VCC_1") (pintype "power_in"))
      (node (ref "IC7") (pin "6") (pinfunction "VREF_6") (pintype "input"))
      (node (ref "IC8") (pin "1") (pinfunction "VCC_1") (pintype "power_in"))
      (node (ref "IC8") (pin "6") (pinfunction "VREF_6") (pintype "input"))
      (node (ref "IC9") (pin "1") (pinfunction "VCC_1") (pintype "power_in"))
      (node (ref "IC9") (pin "6") (pinfunction "VREF_6") (pintype "input"))
      (node (ref "JP1") (pin "1") (pinfunction "1_1") (pintype "passive"))
      (node (ref "JP3") (pin "1") (pinfunction "1_1") (pintype "passive"))
      (node (ref "JP7") (pin "4") (pinfunction "4_4") (pintype "passive"))
      (node (ref "LED1") (pin "1") (pinfunction "A_1") (pintype "passive"))
      (node (ref "R1") (pin "1") (pinfunction "1_1") (pintype "passive"))
      (node (ref "R2") (pin "1") (pinfunction "1_1") (pintype "passive"))
    )
    (net (code "103") (name "VREF") (class "Default")
      (node (ref "IC11") (pin "10") (pinfunction "+IN_10") (pintype "input"))
      (node (ref "IC11") (pin "12") (pinfunction "+IN_12") (pintype "input"))
      (node (ref "IC11") (pin "3") (pinfunction "+IN_3") (pintype "input"))
      (node (ref "IC11") (pin "5") (pinfunction "+IN_5") (pintype "input"))
      (node (ref "IC12") (pin "10") (pinfunction "+IN_10") (pintype "input"))
      (node (ref "IC12") (pin "12") (pinfunction "+IN_12") (pintype "input"))
      (node (ref "IC12") (pin "3") (pinfunction "+IN_3") (pintype "input"))
      (node (ref "R34") (pin "2") (pinfunction "2_2") (pintype "passive"))
      (node (ref "R35") (pin "1") (pinfunction "1_1") (pintype "passive"))
    )
    (net (code "104") (name "unconnected-(IC1-(AIN0{slash}INT2)PB2-Pad3)") (class "Default")
      (node (ref "IC1") (pin "3") (pinfunction "(AIN0/INT2)PB2_3") (pintype "bidirectional"))
    )
    (net (code "105") (name "unconnected-(IC1-(AIN1{slash}OC0)PB3-Pad4)") (class "Default")
      (node (ref "IC1") (pin "4") (pinfunction "(AIN1/OC0)PB3_4") (pintype "bidirectional"))
    )
    (net (code "106") (name "unconnected-(IC1-(INT0)PD2-Pad16)") (class "Default")
      (node (ref "IC1") (pin "16") (pinfunction "(INT0)PD2_16") (pintype "bidirectional"))
    )
    (net (code "107") (name "unconnected-(IC1-(INT1)PD3-Pad17)") (class "Default")
      (node (ref "IC1") (pin "17") (pinfunction "(INT1)PD3_17") (pintype "bidirectional"))
    )
    (net (code "108") (name "unconnected-(IC1-(OC1B)PD4-Pad18)") (class "Default")
      (node (ref "IC1") (pin "18") (pinfunction "(OC1B)PD4_18") (pintype "bidirectional"))
    )
    (net (code "109") (name "unconnected-(IC1-(SS)PB4-Pad5)") (class "Default")
      (node (ref "IC1") (pin "5") (pinfunction "(SS)PB4_5") (pintype "bidirectional"))
    )
    (net (code "110") (name "unconnected-(IC2A-R2OUT-Pad9)") (class "Default")
      (node (ref "IC2") (pin "9") (pinfunction "R2OUT_9") (pintype "output"))
    )
    (net (code "111") (name "unconnected-(IC2A-T2OUT-Pad7)") (class "Default")
      (node (ref "IC2") (pin "7") (pinfunction "T2OUT_7") (pintype "output"))
    )
    (net (code "112") (name "unconnected-(X1-Pad-2)") (class "Default")
      (node (ref "X1") (pin "-2") (pinfunction "-2_-2") (pintype "passive"))
    )
    (net (code "113") (name "unconnected-(X2-Pad4)") (class "Default")
      (node (ref "X2") (pin "4") (pinfunction "4_4") (pintype "passive"))
    )
    (net (code "114") (name "unconnected-(X2-Pad5)") (class "Default")
      (node (ref "X2") (pin "5") (pinfunction "5_5") (pintype "passive"))
    )
    (net (code "115") (name "unconnected-(X3-Pad4)") (class "Default")
      (node (ref "X3") (pin "4") (pinfunction "4_4") (pintype "passive"))
    )
    (net (code "116") (name "unconnected-(X3-Pad5)") (class "Default")
      (node (ref "X3") (pin "5") (pinfunction "5_5") (pintype "passive"))
    )
    (net (code "117") (name "unconnected-(X4-Pad1)") (class "Default")
      (node (ref "X4") (pin "1") (pinfunction "1_1") (pintype "passive"))
    )
    (net (code "118") (name "unconnected-(X4-Pad4)") (class "Default")
      (node (ref "X4") (pin "4") (pinfunction "4_4") (pintype "passive"))
    )
    (net (code "119") (name "unconnected-(X4-Pad6)") (class "Default")
      (node (ref "X4") (pin "6") (pinfunction "6_6") (pintype "passive"))
    )
    (net (code "120") (name "unconnected-(X4-Pad7)") (class "Default")
      (node (ref "X4") (pin "7") (pinfunction "7_7") (pintype "passive"))
    )
    (net (code "121") (name "unconnected-(X4-Pad8)") (class "Default")
      (node (ref "X4") (pin "8") (pinfunction "8_8") (pintype "passive"))
    )
    (net (code "122") (name "unconnected-(X4-Pad9)") (class "Default")
      (node (ref "X4") (pin "9") (pinfunction "9_9") (pintype "passive"))
    )
  )
)
